# 17_CAN_BUS.net
KiCad netlist of a schematic drawn in Altium Designer
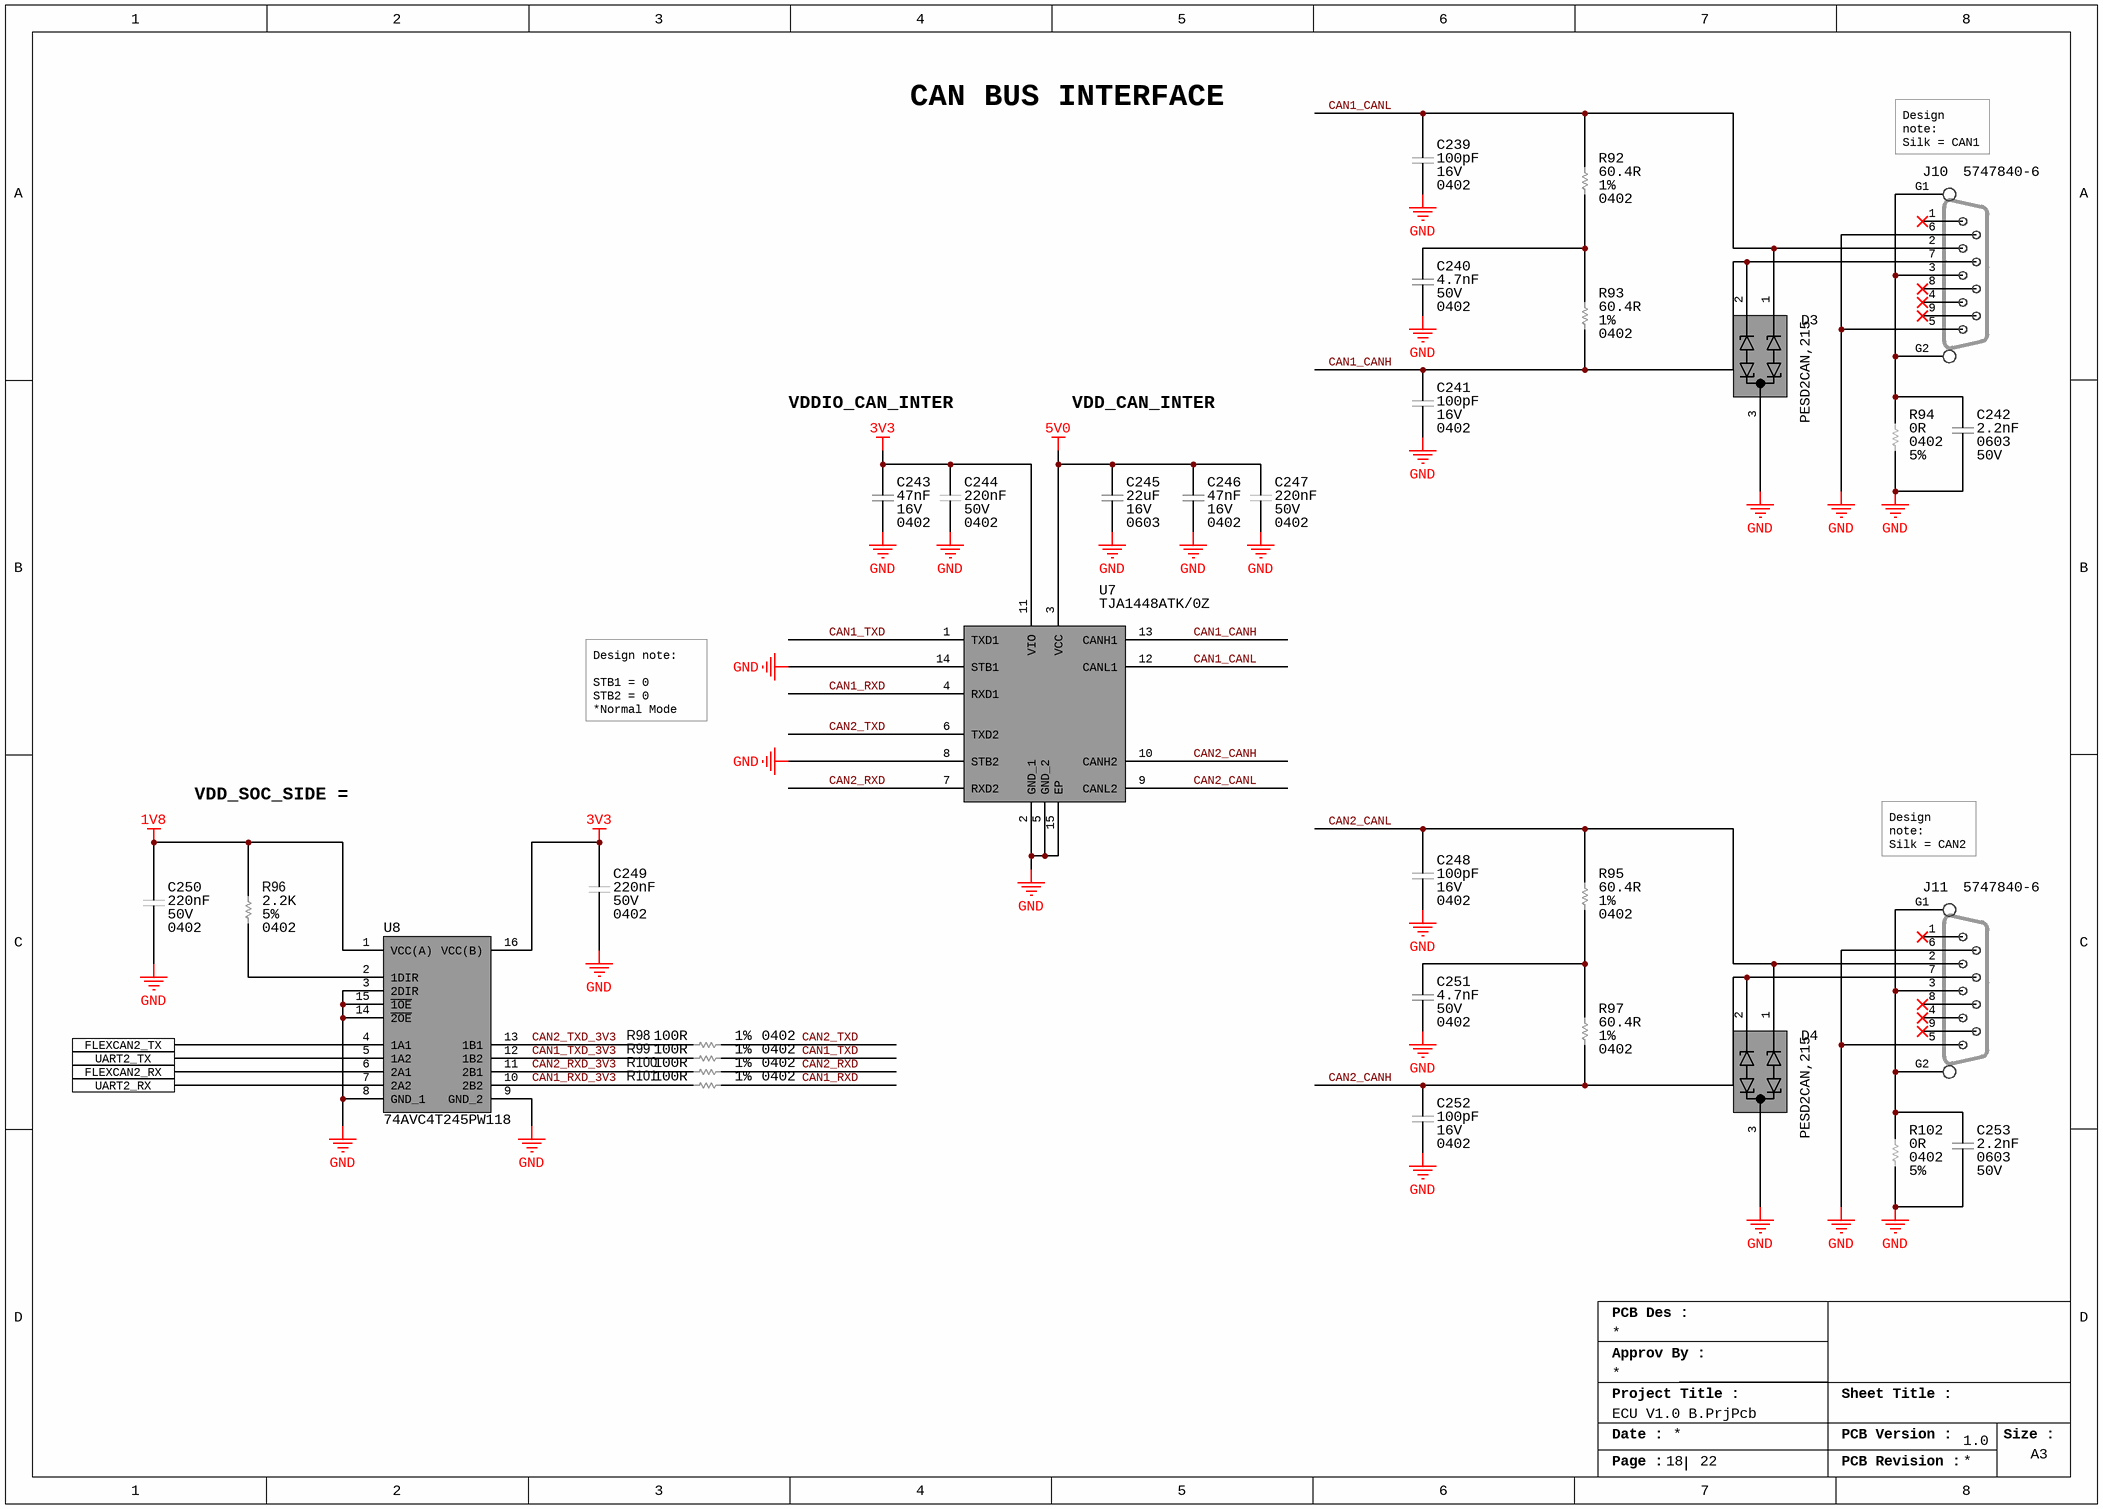
[diagram p0: 17_CAN_BUS.SchDoc]

(export (version "E")
  (design (tool "Eeschema 10.0.6"))
  (components
    (comp (ref "C239")
      (value "CC0402JRNPO7BN101")
      (footprint "CAP_0402_CAPC1005X05N")
      (description "0402 100 pF 16 V ±5 % Tolerance NP0 SMT Multilayer Ceramic Capacitor")
      (fields
        (field (name "MANUFACTURER") "Yageo")
        (field (name "TOLERANCE") "5%")
        (field (name "VOLTAGE RATING (DC)") "16V")
        (field (name "CAPACITANCE") "100pF")
        (field (name "CASE/PACKAGE") "0402")
      )
      (libsource (lib "Electronic Devices_LIB") (part "CAP_100PF_16V_NP0_0402"))
    )
    (comp (ref "C240")
      (value "GRM155R61H472KA01D")
      (footprint "CAP_0402_CAPC1005X05N")
      (description "Multilayer Ceramic Capacitor, 100 uF, 16 V, ± 20%, X5R, 1210 [3225 Metric]")
      (fields
        (field (name "MANUFACTURER") "Murata")
        (field (name "TOLERANCE") "10%")
        (field (name "VOLTAGE RATING") "50V")
        (field (name "CAPACITANCE") "4.7nF")
        (field (name "CASE/PACKAGE") "0402")
      )
      (libsource (lib "Electronic Devices_LIB") (part "CAP_4700PF_50V_X5R_0402"))
    )
    (comp (ref "C241")
      (value "CC0402JRNPO7BN101")
      (footprint "CAP_0402_CAPC1005X05N")
      (description "0402 100 pF 16 V ±5 % Tolerance NP0 SMT Multilayer Ceramic Capacitor")
      (fields
        (field (name "MANUFACTURER") "Yageo")
        (field (name "TOLERANCE") "5%")
        (field (name "VOLTAGE RATING (DC)") "16V")
        (field (name "CAPACITANCE") "100pF")
        (field (name "CASE/PACKAGE") "0402")
      )
      (libsource (lib "Electronic Devices_LIB") (part "CAP_100PF_16V_NP0_0402"))
    )
    (comp (ref "C242")
      (value "GRM1885C1H222JA01D")
      (footprint "CAP_0603_CAPC1608X08N")
      (description "Multilayer Ceramic Capacitor, 2200 pF, 50 V, ï¿½ 5%, C0G (NP0), 0603 [1608 Metric]")
      (fields
        (field (name "MANUFACTURER") "Murata")
        (field (name "TOLERANCE") "5%")
        (field (name "CASE/PACKAGE") "0603")
        (field (name "VOLTAGE RATING") "50V")
        (field (name "CAPACITANCE") "2.2nF")
      )
      (libsource (lib "Electronic Devices_LIB") (part "CAP_2.2nF_50V_NP0_0402"))
    )
    (comp (ref "C243")
      (value "GCM155R71C473KA37D")
      (footprint "CAP_0402_CAPC1005X05N")
      (description "Multilayer Ceramic Capacitor, 0.047 uF, 16 V, ± 10%, X7R, 0402 [1005 Metric]")
      (fields
        (field (name "MANUFACTURER") "Murata")
        (field (name "TOLERANCE") "10%")
        (field (name "CAPACITANCE") "47nF")
        (field (name "VOLTAGE RATING") "16V")
        (field (name "CASE/PACKAGE") "0402")
      )
      (libsource (lib "Electronic Devices_LIB") (part "CAP_47nF_16V_X7R_0402"))
    )
    (comp (ref "C244")
      (value "GRM155R61H224KE01W")
      (footprint "CAP_0402_CAPC1005X05N")
      (description "Multilayer Ceramic Capacitor, 0.22 uF, 50 VDC, ± 10%, X5R, 0402 [1005 Metric]")
      (fields
        (field (name "MANUFACTURER") "Murata")
        (field (name "CASE/PACKAGE") "0402")
        (field (name "VOLTAGE RATING (DC)") "50V")
        (field (name "CAPACITANCE") "220nF")
      )
      (libsource (lib "Electronic Devices_LIB") (part "CAP_0.22UF_50V_X5R_0402"))
    )
    (comp (ref "C245")
      (value "CL10A226MO7JZNC")
      (footprint "CAP_0603_CAPC1608X08N")
      (description "Cap Ceramic 22uF 16V X5R 20% Pad SMD 0603 85C T/R")
      (fields
        (field (name "MANUFACTURER") "Samsung")
        (field (name "TOLERANCE") "20%")
        (field (name "CAPACITANCE") "22uF")
        (field (name "VOLTAGE RATING") "16V")
        (field (name "CASE/PACKAGE") "0603")
      )
      (libsource (lib "Electronic Devices_LIB") (part "CAP_22UF_16V_X5R_0603"))
    )
    (comp (ref "C246")
      (value "GCM155R71C473KA37D")
      (footprint "CAP_0402_CAPC1005X05N")
      (description "Multilayer Ceramic Capacitor, 0.047 uF, 16 V, ± 10%, X7R, 0402 [1005 Metric]")
      (fields
        (field (name "MANUFACTURER") "Murata")
        (field (name "TOLERANCE") "10%")
        (field (name "CAPACITANCE") "47nF")
        (field (name "VOLTAGE RATING") "16V")
        (field (name "CASE/PACKAGE") "0402")
      )
      (libsource (lib "Electronic Devices_LIB") (part "CAP_47nF_16V_X7R_0402"))
    )
    (comp (ref "C247")
      (value "GRM155R61H224KE01W")
      (footprint "CAP_0402_CAPC1005X05N")
      (description "Multilayer Ceramic Capacitor, 0.22 uF, 50 VDC, ± 10%, X5R, 0402 [1005 Metric]")
      (fields
        (field (name "MANUFACTURER") "Murata")
        (field (name "CASE/PACKAGE") "0402")
        (field (name "VOLTAGE RATING (DC)") "50V")
        (field (name "CAPACITANCE") "220nF")
      )
      (libsource (lib "Electronic Devices_LIB") (part "CAP_0.22UF_50V_X5R_0402"))
    )
    (comp (ref "C248")
      (value "CC0402JRNPO7BN101")
      (footprint "CAP_0402_CAPC1005X05N")
      (description "0402 100 pF 16 V ±5 % Tolerance NP0 SMT Multilayer Ceramic Capacitor")
      (fields
        (field (name "MANUFACTURER") "Yageo")
        (field (name "TOLERANCE") "5%")
        (field (name "VOLTAGE RATING (DC)") "16V")
        (field (name "CAPACITANCE") "100pF")
        (field (name "CASE/PACKAGE") "0402")
      )
      (libsource (lib "Electronic Devices_LIB") (part "CAP_100PF_16V_NP0_0402"))
    )
    (comp (ref "C249")
      (value "GRM155R61H224KE01W")
      (footprint "CAP_0402_CAPC1005X05N")
      (description "Multilayer Ceramic Capacitor, 0.22 uF, 50 VDC, ± 10%, X5R, 0402 [1005 Metric]")
      (fields
        (field (name "MANUFACTURER") "Murata")
        (field (name "CASE/PACKAGE") "0402")
        (field (name "VOLTAGE RATING (DC)") "50V")
        (field (name "CAPACITANCE") "220nF")
      )
      (libsource (lib "Electronic Devices_LIB") (part "CAP_0.22UF_50V_X5R_0402"))
    )
    (comp (ref "C250")
      (value "GRM155R61H224KE01W")
      (footprint "CAP_0402_CAPC1005X05N")
      (description "Multilayer Ceramic Capacitor, 0.22 uF, 50 VDC, ± 10%, X5R, 0402 [1005 Metric]")
      (fields
        (field (name "MANUFACTURER") "Murata")
        (field (name "CASE/PACKAGE") "0402")
        (field (name "VOLTAGE RATING (DC)") "50V")
        (field (name "CAPACITANCE") "220nF")
      )
      (libsource (lib "Electronic Devices_LIB") (part "CAP_0.22UF_50V_X5R_0402"))
    )
    (comp (ref "C251")
      (value "GRM155R61H472KA01D")
      (footprint "CAP_0402_CAPC1005X05N")
      (description "Multilayer Ceramic Capacitor, 100 uF, 16 V, ± 20%, X5R, 1210 [3225 Metric]")
      (fields
        (field (name "MANUFACTURER") "Murata")
        (field (name "TOLERANCE") "10%")
        (field (name "VOLTAGE RATING") "50V")
        (field (name "CAPACITANCE") "4.7nF")
        (field (name "CASE/PACKAGE") "0402")
      )
      (libsource (lib "Electronic Devices_LIB") (part "CAP_4700PF_50V_X5R_0402"))
    )
    (comp (ref "C252")
      (value "CC0402JRNPO7BN101")
      (footprint "CAP_0402_CAPC1005X05N")
      (description "0402 100 pF 16 V ±5 % Tolerance NP0 SMT Multilayer Ceramic Capacitor")
      (fields
        (field (name "MANUFACTURER") "Yageo")
        (field (name "TOLERANCE") "5%")
        (field (name "VOLTAGE RATING (DC)") "16V")
        (field (name "CAPACITANCE") "100pF")
        (field (name "CASE/PACKAGE") "0402")
      )
      (libsource (lib "Electronic Devices_LIB") (part "CAP_100PF_16V_NP0_0402"))
    )
    (comp (ref "C253")
      (value "GRM1885C1H222JA01D")
      (footprint "CAP_0603_CAPC1608X08N")
      (description "Multilayer Ceramic Capacitor, 2200 pF, 50 V, ï¿½ 5%, C0G (NP0), 0603 [1608 Metric]")
      (fields
        (field (name "MANUFACTURER") "Murata")
        (field (name "TOLERANCE") "5%")
        (field (name "CASE/PACKAGE") "0603")
        (field (name "VOLTAGE RATING") "50V")
        (field (name "CAPACITANCE") "2.2nF")
      )
      (libsource (lib "Electronic Devices_LIB") (part "CAP_2.2nF_50V_NP0_0402"))
    )
    (comp (ref "D3")
      (value "PESD2CAN,215")
      (footprint "DIO_PESD2CAN,215")
      (description "5A 230W 41V 26.2V Bidirectional 24V SOT-23 ESD and Surge Protection (TVS/ESD) ROHS")
      (fields (field (name "MANUFACTURER") "Nexperia"))
      (libsource (lib "Electronic Devices_LIB") (part "DIO_TVS_41V_5A_PESD2CAN,215"))
    )
    (comp (ref "D4")
      (value "PESD2CAN,215")
      (footprint "DIO_PESD2CAN,215")
      (description "5A 230W 41V 26.2V Bidirectional 24V SOT-23 ESD and Surge Protection (TVS/ESD) ROHS")
      (fields (field (name "MANUFACTURER") "Nexperia"))
      (libsource (lib "Electronic Devices_LIB") (part "DIO_TVS_41V_5A_PESD2CAN,215"))
    )
    (comp (ref "J10")
      (value "5747840-6")
      (footprint "TE_5747840-6")
      (description "D Subminiature Connector, 9 Contact(s), Male, 0.108 inch Pitch, Solder Terminal, #4-40, Plug")
      (fields (field (name "MANUFACTURER") "TE Connectivity"))
      (libsource (lib "Electronic Devices_LIB") (part "CONN_DB9_TEConnectivity_5747840-6"))
    )
    (comp (ref "J11")
      (value "5747840-6")
      (footprint "TE_5747840-6")
      (description "D Subminiature Connector, 9 Contact(s), Male, 0.108 inch Pitch, Solder Terminal, #4-40, Plug")
      (fields (field (name "MANUFACTURER") "TE Connectivity"))
      (libsource (lib "Electronic Devices_LIB") (part "CONN_DB9_TEConnectivity_5747840-6"))
    )
    (comp (ref "R92")
      (value "RK73H1ETTP60R4F")
      (footprint "RES_0402_RESC1005X04N")
      (description "Res Thick Film 0402 60.4 Ohm 1% 0.1W(1/10W) ±100ppm/C Pad SMD Automotive T/R")
      (fields
        (field (name "MANUFACTURER") "KOA Speer")
        (field (name "TOLERANCE") "1%")
        (field (name "RESISTANCE") "60.4R")
        (field (name "CASE/PACKAGE") "0402")
      )
      (libsource (lib "Electronic Devices_LIB") (part "RES_60.4R_1%_100mW_0402"))
    )
    (comp (ref "R93")
      (value "RK73H1ETTP60R4F")
      (footprint "RES_0402_RESC1005X04N")
      (description "Res Thick Film 0402 60.4 Ohm 1% 0.1W(1/10W) ±100ppm/C Pad SMD Automotive T/R")
      (fields
        (field (name "MANUFACTURER") "KOA Speer")
        (field (name "TOLERANCE") "1%")
        (field (name "RESISTANCE") "60.4R")
        (field (name "CASE/PACKAGE") "0402")
      )
      (libsource (lib "Electronic Devices_LIB") (part "RES_60.4R_1%_100mW_0402"))
    )
    (comp (ref "R94")
      (value "ERJ-2GE0R00X")
      (footprint "RES_0402_RESC1005X04N")
      (description "SMD Chip Resistor, Jumper, 0 ohm, 100 mW, 0402 [1005 Metric], Thick Film, General Purpose")
      (fields
        (field (name "MANUFACTURER") "Panasonic")
        (field (name "CASE CODE (IMPERIAL)") "0402")
        (field (name "TOLERANCE") "5%")
        (field (name "RESISTANCE") "0R")
      )
      (libsource (lib "Electronic Devices_LIB") (part "RES_0R_5%_100mW_0402"))
    )
    (comp (ref "R95")
      (value "RK73H1ETTP60R4F")
      (footprint "RES_0402_RESC1005X04N")
      (description "Res Thick Film 0402 60.4 Ohm 1% 0.1W(1/10W) ±100ppm/C Pad SMD Automotive T/R")
      (fields
        (field (name "MANUFACTURER") "KOA Speer")
        (field (name "TOLERANCE") "1%")
        (field (name "RESISTANCE") "60.4R")
        (field (name "CASE/PACKAGE") "0402")
      )
      (libsource (lib "Electronic Devices_LIB") (part "RES_60.4R_1%_100mW_0402"))
    )
    (comp (ref "R96")
      (value "RC0402JR-072K2L")
      (footprint "RES_0402_RESC1005X04N")
      (description "SMD Chip Resistor, 2.2 kOhm, ± 5%, 63 mW, 0402 [1005 Metric], Thick Film, General Purpose")
      (fields
        (field (name "MANUFACTURER") "Yageo")
        (field (name "TOLERANCE") "5%")
        (field (name "RESISTANCE") "2.2K")
        (field (name "CASE/PACKAGE") "0402")
      )
      (libsource (lib "Electronic Devices_LIB") (part "RES_2.2K_5%_63mW_0402"))
    )
    (comp (ref "R97")
      (value "RK73H1ETTP60R4F")
      (footprint "RES_0402_RESC1005X04N")
      (description "Res Thick Film 0402 60.4 Ohm 1% 0.1W(1/10W) ±100ppm/C Pad SMD Automotive T/R")
      (fields
        (field (name "MANUFACTURER") "KOA Speer")
        (field (name "TOLERANCE") "1%")
        (field (name "RESISTANCE") "60.4R")
        (field (name "CASE/PACKAGE") "0402")
      )
      (libsource (lib "Electronic Devices_LIB") (part "RES_60.4R_1%_100mW_0402"))
    )
    (comp (ref "R98")
      (value "ERJ-2RKF1000X")
      (footprint "RES_0402_RESC1005X04N")
      (description "Resistor Thick Film 0402 100 Ohm 1% 1/10W 100ppm/C Molded SMD Punched Carrier T/R")
      (fields
        (field (name "MANUFACTURER") "Panasonic")
        (field (name "TOLERANCE") "1%")
        (field (name "RESISTANCE") "100R")
        (field (name "CASE/PACKAGE") "0402")
      )
      (libsource (lib "Electronic Devices_LIB") (part "RES_100R_1%_100mW_0402"))
    )
    (comp (ref "R99")
      (value "ERJ-2RKF1000X")
      (footprint "RES_0402_RESC1005X04N")
      (description "Resistor Thick Film 0402 100 Ohm 1% 1/10W 100ppm/C Molded SMD Punched Carrier T/R")
      (fields
        (field (name "MANUFACTURER") "Panasonic")
        (field (name "TOLERANCE") "1%")
        (field (name "RESISTANCE") "100R")
        (field (name "CASE/PACKAGE") "0402")
      )
      (libsource (lib "Electronic Devices_LIB") (part "RES_100R_1%_100mW_0402"))
    )
    (comp (ref "R100")
      (value "ERJ-2RKF1000X")
      (footprint "RES_0402_RESC1005X04N")
      (description "Resistor Thick Film 0402 100 Ohm 1% 1/10W 100ppm/C Molded SMD Punched Carrier T/R")
      (fields
        (field (name "MANUFACTURER") "Panasonic")
        (field (name "TOLERANCE") "1%")
        (field (name "RESISTANCE") "100R")
        (field (name "CASE/PACKAGE") "0402")
      )
      (libsource (lib "Electronic Devices_LIB") (part "RES_100R_1%_100mW_0402"))
    )
    (comp (ref "R101")
      (value "ERJ-2RKF1000X")
      (footprint "RES_0402_RESC1005X04N")
      (description "Resistor Thick Film 0402 100 Ohm 1% 1/10W 100ppm/C Molded SMD Punched Carrier T/R")
      (fields
        (field (name "MANUFACTURER") "Panasonic")
        (field (name "TOLERANCE") "1%")
        (field (name "RESISTANCE") "100R")
        (field (name "CASE/PACKAGE") "0402")
      )
      (libsource (lib "Electronic Devices_LIB") (part "RES_100R_1%_100mW_0402"))
    )
    (comp (ref "R102")
      (value "ERJ-2GE0R00X")
      (footprint "RES_0402_RESC1005X04N")
      (description "SMD Chip Resistor, Jumper, 0 ohm, 100 mW, 0402 [1005 Metric], Thick Film, General Purpose")
      (fields
        (field (name "MANUFACTURER") "Panasonic")
        (field (name "CASE CODE (IMPERIAL)") "0402")
        (field (name "TOLERANCE") "5%")
        (field (name "RESISTANCE") "0R")
      )
      (libsource (lib "Electronic Devices_LIB") (part "RES_0R_5%_100mW_0402"))
    )
    (comp (ref "U7")
      (value "TJA1448ATK/0Z")
      (footprint "SON65P300X450X100-15N")
      (description "Can Transceiver with Standby Mode Dual High-Speed 5Mbps 4.5V to 5.5V 14-Pin HVSON")
      (fields (field (name "MANUFACTURER") "NXP Semiconductors"))
      (libsource (lib "Electronic Devices_LIB") (part "IC_TRANSCEIVER_CAN_TJA1448ATK/0Z"))
    )
    (comp (ref "U8")
      (value "74AVC4T245PW118")
      (footprint "SOP65P640X110-16N")
      (description "74Avc4T245Pw/Sot403/Tssop16 Rohs Compliant: Yes ¦Nexperia 74AVC4T245PW 118")
      (fields (field (name "MANUFACTURER") "Nexperia"))
      (libsource (lib "Electronic Devices_LIB") (part "IC_TRANSLATION_TXRX_74AVC4T245PW118"))
    )
  )
  (nets
    (net (code "1") (name "/CAN1_CANH") (class "Default")
      (node (ref "C241") (pin "2") (pinfunction "2_2") (pintype "passive"))
      (node (ref "D3") (pin "2") (pinfunction "C2_2") (pintype "passive"))
      (node (ref "J10") (pin "7") (pinfunction "7_7") (pintype "passive"))
      (node (ref "R93") (pin "1") (pinfunction "1_1") (pintype "passive"))
      (node (ref "U7") (pin "13") (pinfunction "CANH1_13") (pintype "passive"))
    )
    (net (code "2") (name "/CAN1_CANL") (class "Default")
      (node (ref "C239") (pin "2") (pinfunction "2_2") (pintype "passive"))
      (node (ref "D3") (pin "1") (pinfunction "C1_1") (pintype "passive"))
      (node (ref "J10") (pin "2") (pinfunction "2_2") (pintype "passive"))
      (node (ref "R92") (pin "2") (pinfunction "2_2") (pintype "passive"))
      (node (ref "U7") (pin "12") (pinfunction "CANL1_12") (pintype "passive"))
    )
    (net (code "3") (name "/CAN1_RXD") (class "Default")
      (node (ref "R101") (pin "2") (pinfunction "2_2") (pintype "passive"))
      (node (ref "U7") (pin "4") (pinfunction "RXD1_4") (pintype "passive"))
    )
    (net (code "4") (name "/CAN1_RXD_3V3") (class "Default")
      (node (ref "R101") (pin "1") (pinfunction "1_1") (pintype "passive"))
      (node (ref "U8") (pin "10") (pinfunction "2B2_10") (pintype "passive"))
    )
    (net (code "5") (name "/CAN1_TXD") (class "Default")
      (node (ref "R99") (pin "2") (pinfunction "2_2") (pintype "passive"))
      (node (ref "U7") (pin "1") (pinfunction "TXD1_1") (pintype "passive"))
    )
    (net (code "6") (name "/CAN1_TXD_3V3") (class "Default")
      (node (ref "R99") (pin "1") (pinfunction "1_1") (pintype "passive"))
      (node (ref "U8") (pin "12") (pinfunction "1B2_12") (pintype "passive"))
    )
    (net (code "7") (name "/CAN2_CANH") (class "Default")
      (node (ref "C252") (pin "2") (pinfunction "2_2") (pintype "passive"))
      (node (ref "D4") (pin "2") (pinfunction "C2_2") (pintype "passive"))
      (node (ref "J11") (pin "7") (pinfunction "7_7") (pintype "passive"))
      (node (ref "R97") (pin "1") (pinfunction "1_1") (pintype "passive"))
      (node (ref "U7") (pin "10") (pinfunction "CANH2_10") (pintype "passive"))
    )
    (net (code "8") (name "/CAN2_CANL") (class "Default")
      (node (ref "C248") (pin "2") (pinfunction "2_2") (pintype "passive"))
      (node (ref "D4") (pin "1") (pinfunction "C1_1") (pintype "passive"))
      (node (ref "J11") (pin "2") (pinfunction "2_2") (pintype "passive"))
      (node (ref "R95") (pin "2") (pinfunction "2_2") (pintype "passive"))
      (node (ref "U7") (pin "9") (pinfunction "CANL2_9") (pintype "passive"))
    )
    (net (code "9") (name "/CAN2_RXD") (class "Default")
      (node (ref "R100") (pin "2") (pinfunction "2_2") (pintype "passive"))
      (node (ref "U7") (pin "7") (pinfunction "RXD2_7") (pintype "passive"))
    )
    (net (code "10") (name "/CAN2_RXD_3V3") (class "Default")
      (node (ref "R100") (pin "1") (pinfunction "1_1") (pintype "passive"))
      (node (ref "U8") (pin "11") (pinfunction "2B1_11") (pintype "passive"))
    )
    (net (code "11") (name "/CAN2_TXD") (class "Default")
      (node (ref "R98") (pin "2") (pinfunction "2_2") (pintype "passive"))
      (node (ref "U7") (pin "6") (pinfunction "TXD2_6") (pintype "passive"))
    )
    (net (code "12") (name "/CAN2_TXD_3V3") (class "Default")
      (node (ref "R98") (pin "1") (pinfunction "1_1") (pintype "passive"))
      (node (ref "U8") (pin "13") (pinfunction "1B1_13") (pintype "passive"))
    )
    (net (code "13") (name "/FLEXCAN2_RX") (class "Default")
      (node (ref "U8") (pin "6") (pinfunction "2A1_6") (pintype "passive"))
    )
    (net (code "14") (name "/FLEXCAN2_TX") (class "Default")
      (node (ref "U8") (pin "4") (pinfunction "1A1_4") (pintype "passive"))
    )
    (net (code "15") (name "/UART2_RX") (class "Default")
      (node (ref "U8") (pin "7") (pinfunction "2A2_7") (pintype "passive"))
    )
    (net (code "16") (name "/UART2_TX") (class "Default")
      (node (ref "U8") (pin "5") (pinfunction "1A2_5") (pintype "passive"))
    )
    (net (code "17") (name "1V8") (class "Default")
      (node (ref "C250") (pin "2") (pinfunction "2_2") (pintype "passive"))
      (node (ref "R96") (pin "2") (pinfunction "2_2") (pintype "passive"))
      (node (ref "U8") (pin "1") (pinfunction "VCC(A)_1") (pintype "passive"))
    )
    (net (code "18") (name "3V3") (class "Default")
      (node (ref "C243") (pin "2") (pinfunction "2_2") (pintype "passive"))
      (node (ref "C244") (pin "1") (pinfunction "1_1") (pintype "passive"))
      (node (ref "C249") (pin "2") (pinfunction "2_2") (pintype "passive"))
      (node (ref "U7") (pin "11") (pinfunction "VIO_11") (pintype "passive"))
      (node (ref "U8") (pin "16") (pinfunction "VCC(B)_16") (pintype "passive"))
    )
    (net (code "19") (name "5V0") (class "Default")
      (node (ref "C245") (pin "2") (pinfunction "2_2") (pintype "passive"))
      (node (ref "C246") (pin "2") (pinfunction "2_2") (pintype "passive"))
      (node (ref "C247") (pin "1") (pinfunction "1_1") (pintype "passive"))
      (node (ref "U7") (pin "3") (pinfunction "VCC_3") (pintype "passive"))
    )
    (net (code "20") (name "GND") (class "Default")
      (node (ref "C239") (pin "1") (pinfunction "1_1") (pintype "passive"))
      (node (ref "C240") (pin "1") (pinfunction "1_1") (pintype "passive"))
      (node (ref "C241") (pin "1") (pinfunction "1_1") (pintype "passive"))
      (node (ref "C242") (pin "1") (pinfunction "1_1") (pintype "passive"))
      (node (ref "C243") (pin "1") (pinfunction "1_1") (pintype "passive"))
      (node (ref "C244") (pin "2") (pinfunction "2_2") (pintype "passive"))
      (node (ref "C245") (pin "1") (pinfunction "1_1") (pintype "passive"))
      (node (ref "C246") (pin "1") (pinfunction "1_1") (pintype "passive"))
      (node (ref "C247") (pin "2") (pinfunction "2_2") (pintype "passive"))
      (node (ref "C248") (pin "1") (pinfunction "1_1") (pintype "passive"))
      (node (ref "C249") (pin "1") (pinfunction "1_1") (pintype "passive"))
      (node (ref "C250") (pin "1") (pinfunction "1_1") (pintype "passive"))
      (node (ref "C251") (pin "1") (pinfunction "1_1") (pintype "passive"))
      (node (ref "C252") (pin "1") (pinfunction "1_1") (pintype "passive"))
      (node (ref "C253") (pin "1") (pinfunction "1_1") (pintype "passive"))
      (node (ref "D3") (pin "3") (pinfunction "CC_3") (pintype "passive"))
      (node (ref "D4") (pin "3") (pinfunction "CC_3") (pintype "passive"))
      (node (ref "J10") (pin "5") (pinfunction "5_5") (pintype "passive"))
      (node (ref "J10") (pin "6") (pinfunction "6_6") (pintype "passive"))
      (node (ref "J11") (pin "5") (pinfunction "5_5") (pintype "passive"))
      (node (ref "J11") (pin "6") (pinfunction "6_6") (pintype "passive"))
      (node (ref "R102") (pin "1") (pinfunction "1_1") (pintype "passive"))
      (node (ref "R94") (pin "1") (pinfunction "1_1") (pintype "passive"))
      (node (ref "U7") (pin "14") (pinfunction "STB1_14") (pintype "passive"))
      (node (ref "U7") (pin "15") (pinfunction "EP_15") (pintype "passive"))
      (node (ref "U7") (pin "2") (pinfunction "GND_1_2") (pintype "passive"))
      (node (ref "U7") (pin "5") (pinfunction "GND_2_5") (pintype "passive"))
      (node (ref "U7") (pin "8") (pinfunction "STB2_8") (pintype "passive"))
      (node (ref "U8") (pin "14") (pinfunction "~{2OE}_14") (pintype "passive"))
      (node (ref "U8") (pin "15") (pinfunction "~{1OE}_15") (pintype "passive"))
      (node (ref "U8") (pin "3") (pinfunction "2DIR_3") (pintype "passive"))
      (node (ref "U8") (pin "8") (pinfunction "GND_1_8") (pintype "passive"))
      (node (ref "U8") (pin "9") (pinfunction "GND_2_9") (pintype "passive"))
    )
    (net (code "21") (name "Net-(C240-Pad2)") (class "Default")
      (node (ref "C240") (pin "2") (pinfunction "2_2") (pintype "passive"))
      (node (ref "R92") (pin "1") (pinfunction "1_1") (pintype "passive"))
      (node (ref "R93") (pin "2") (pinfunction "2_2") (pintype "passive"))
    )
    (net (code "22") (name "Net-(C251-Pad2)") (class "Default")
      (node (ref "C251") (pin "2") (pinfunction "2_2") (pintype "passive"))
      (node (ref "R95") (pin "1") (pinfunction "1_1") (pintype "passive"))
      (node (ref "R97") (pin "2") (pinfunction "2_2") (pintype "passive"))
    )
    (net (code "23") (name "Net-(J10-G)") (class "Default")
      (node (ref "C242") (pin "2") (pinfunction "2_2") (pintype "passive"))
      (node (ref "J10") (pin "3") (pinfunction "3_3") (pintype "passive"))
      (node (ref "J10") (pin "G1") (pinfunction "G1_G1") (pintype "passive"))
      (node (ref "J10") (pin "G2") (pinfunction "G_G2") (pintype "passive"))
      (node (ref "R94") (pin "2") (pinfunction "2_2") (pintype "passive"))
    )
    (net (code "24") (name "Net-(J11-G)") (class "Default")
      (node (ref "C253") (pin "2") (pinfunction "2_2") (pintype "passive"))
      (node (ref "J11") (pin "3") (pinfunction "3_3") (pintype "passive"))
      (node (ref "J11") (pin "G1") (pinfunction "G1_G1") (pintype "passive"))
      (node (ref "J11") (pin "G2") (pinfunction "G_G2") (pintype "passive"))
      (node (ref "R102") (pin "2") (pinfunction "2_2") (pintype "passive"))
    )
    (net (code "25") (name "Net-(U8-1DIR)") (class "Default")
      (node (ref "R96") (pin "1") (pinfunction "1_1") (pintype "passive"))
      (node (ref "U8") (pin "2") (pinfunction "1DIR_2") (pintype "passive"))
    )
    (net (code "26") (name "unconnected-(J10-Pad1)") (class "Default")
      (node (ref "J10") (pin "1") (pinfunction "1_1") (pintype "passive+no_connect"))
    )
    (net (code "27") (name "unconnected-(J10-Pad4)") (class "Default")
      (node (ref "J10") (pin "4") (pinfunction "4_4") (pintype "passive+no_connect"))
    )
    (net (code "28") (name "unconnected-(J10-Pad8)") (class "Default")
      (node (ref "J10") (pin "8") (pinfunction "8_8") (pintype "passive+no_connect"))
    )
    (net (code "29") (name "unconnected-(J10-Pad9)") (class "Default")
      (node (ref "J10") (pin "9") (pinfunction "9_9") (pintype "passive+no_connect"))
    )
    (net (code "30") (name "unconnected-(J11-Pad1)") (class "Default")
      (node (ref "J11") (pin "1") (pinfunction "1_1") (pintype "passive+no_connect"))
    )
    (net (code "31") (name "unconnected-(J11-Pad4)") (class "Default")
      (node (ref "J11") (pin "4") (pinfunction "4_4") (pintype "passive+no_connect"))
    )
    (net (code "32") (name "unconnected-(J11-Pad8)") (class "Default")
      (node (ref "J11") (pin "8") (pinfunction "8_8") (pintype "passive+no_connect"))
    )
    (net (code "33") (name "unconnected-(J11-Pad9)") (class "Default")
      (node (ref "J11") (pin "9") (pinfunction "9_9") (pintype "passive+no_connect"))
    )
  )
)
